# m2301-stereo-output.net
KiCad netlist of a schematic drawn in EAGLE
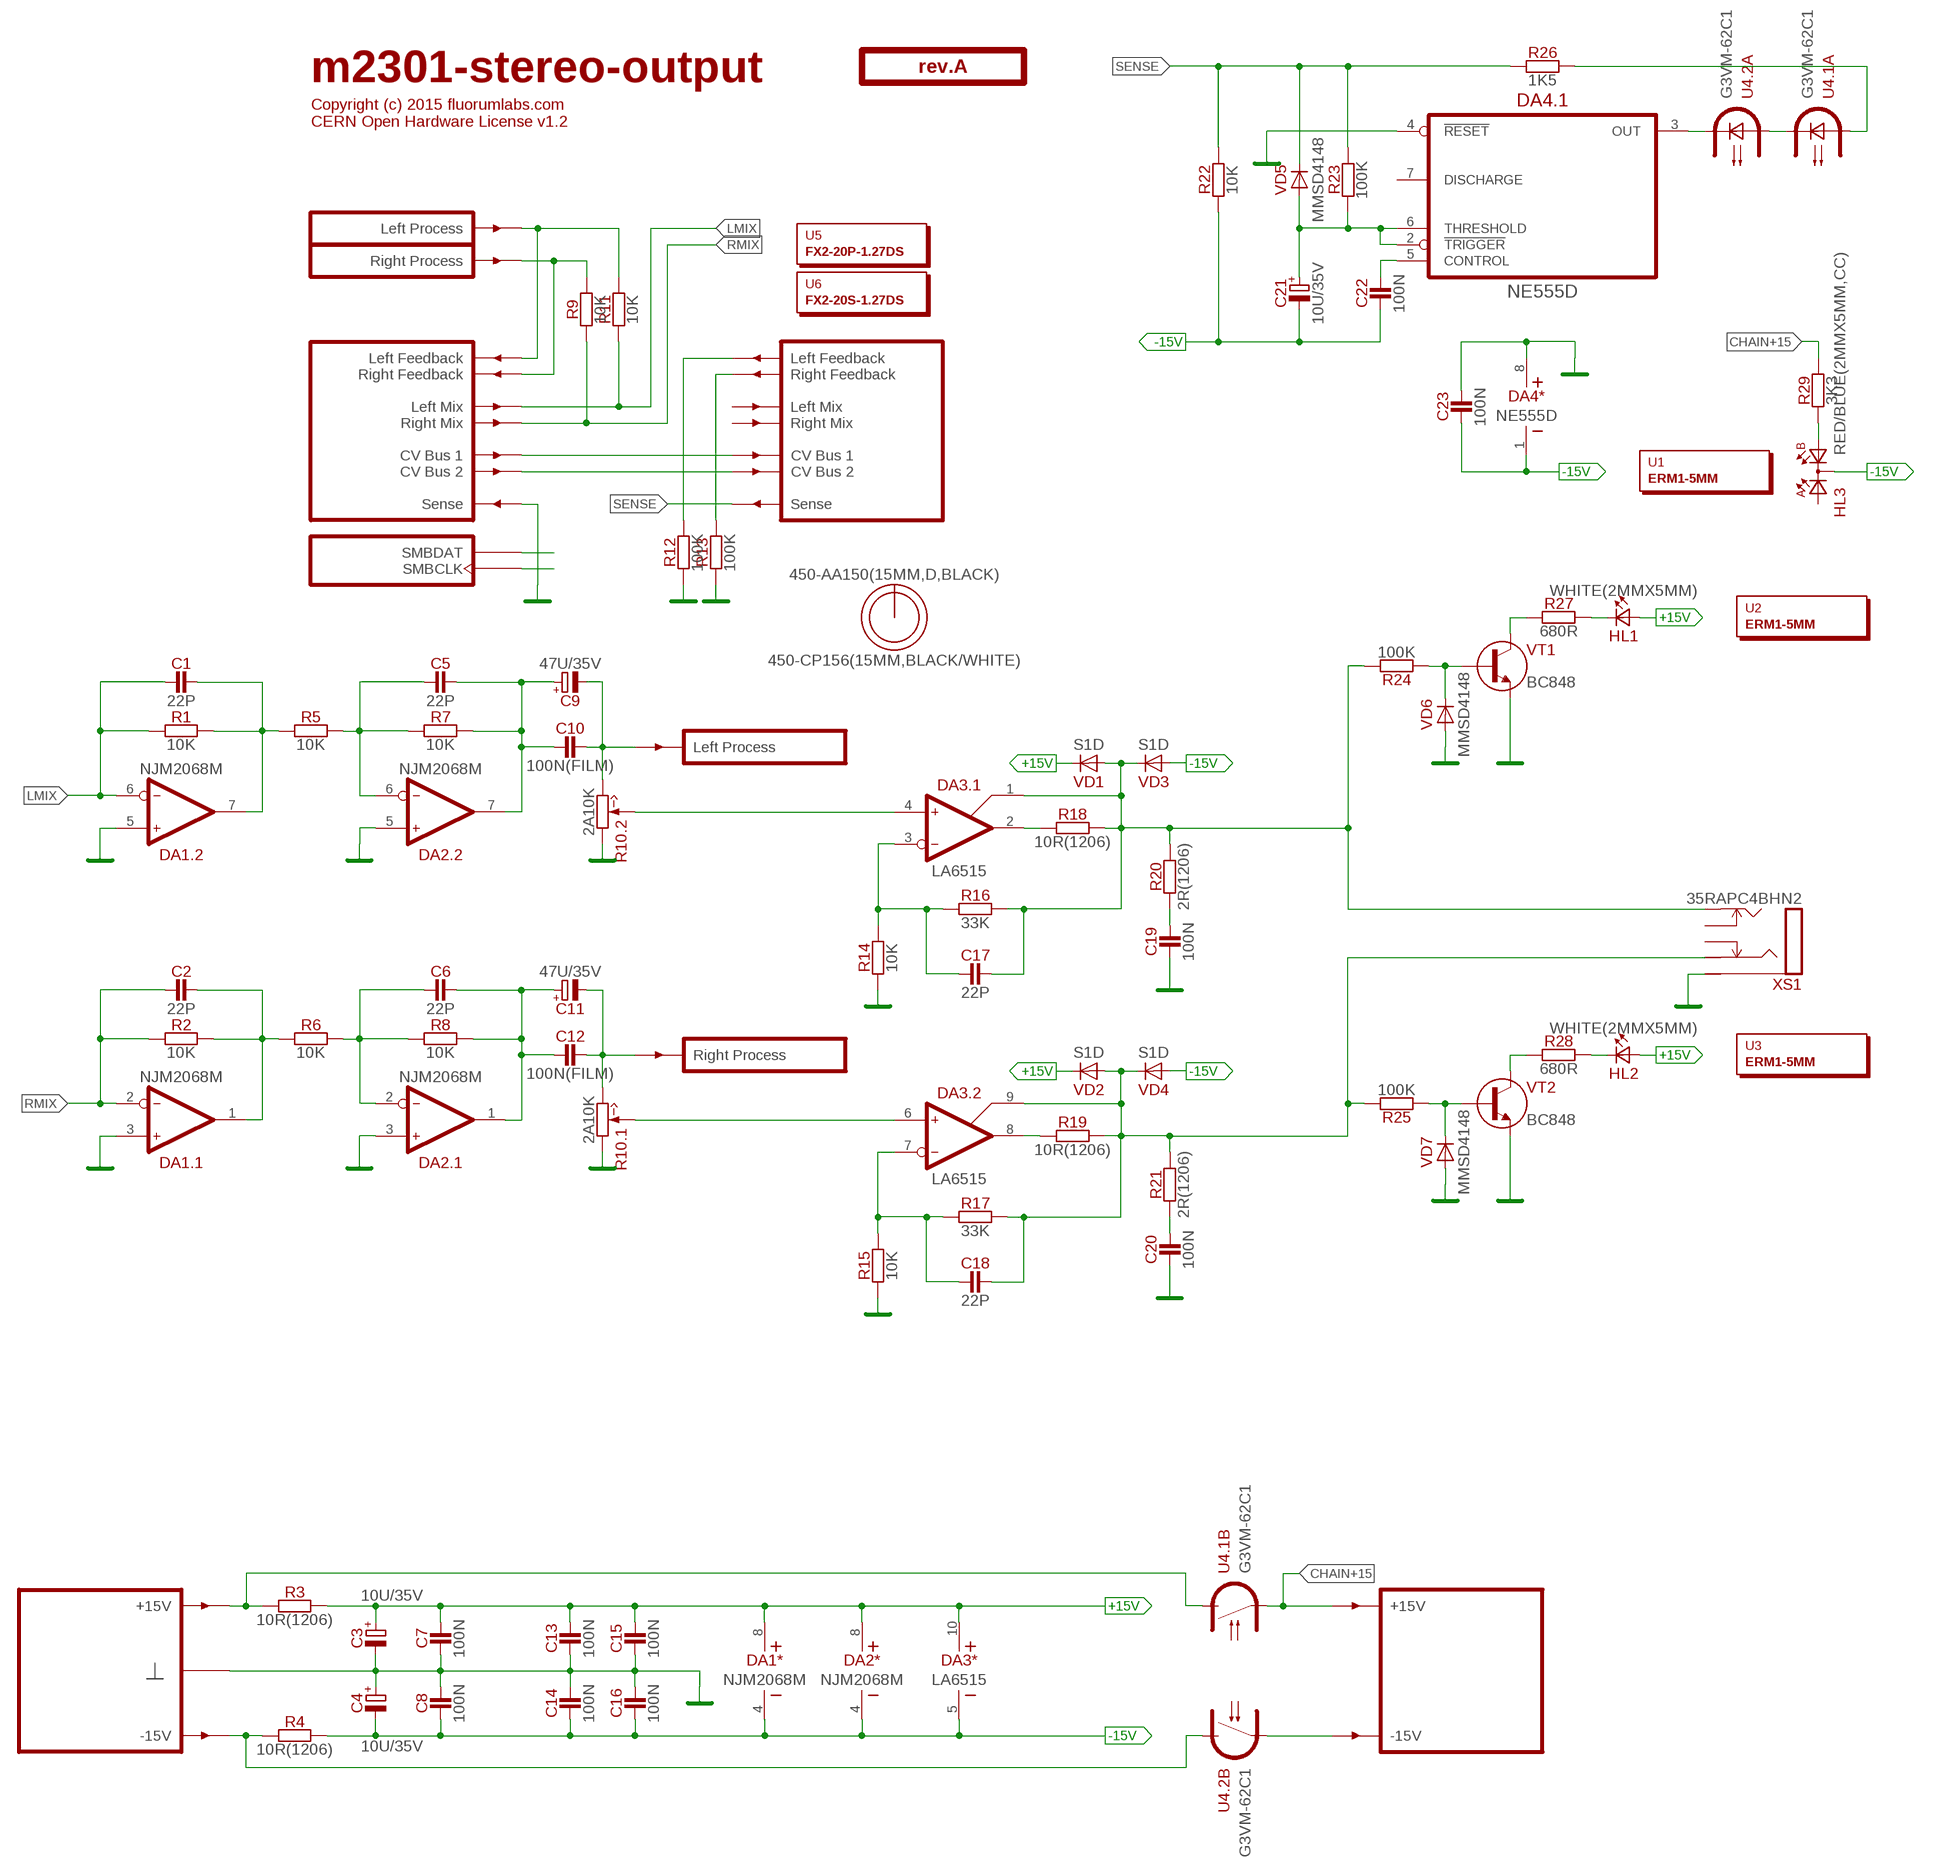
[diagram p0: schematic, sheet 1]

(export (version "E")
  (design (tool "Eeschema 10.0.6"))
  (components
    (comp (ref "C1")
      (value "22P")
      (footprint "eagle-import:C-0805")
      (libsource (lib "eagle-import") (part "?22P"))
    )
    (comp (ref "C2")
      (value "22P")
      (footprint "eagle-import:C-0805")
      (libsource (lib "eagle-import") (part "?22P"))
    )
    (comp (ref "C3")
      (value "10U/35V")
      (footprint "eagle-import:E2-5")
      (libsource (lib "eagle-import") (part "?10U/35V"))
    )
    (comp (ref "C4")
      (value "10U/35V")
      (footprint "eagle-import:E2-5")
      (libsource (lib "eagle-import") (part "?10U/35V"))
    )
    (comp (ref "C5")
      (value "22P")
      (footprint "eagle-import:C-0805")
      (libsource (lib "eagle-import") (part "?22P"))
    )
    (comp (ref "C6")
      (value "22P")
      (footprint "eagle-import:C-0805")
      (libsource (lib "eagle-import") (part "?22P"))
    )
    (comp (ref "C7")
      (value "100N")
      (footprint "eagle-import:C-0805")
      (libsource (lib "eagle-import") (part "?100N"))
    )
    (comp (ref "C8")
      (value "100N")
      (footprint "eagle-import:C-0805")
      (libsource (lib "eagle-import") (part "?100N"))
    )
    (comp (ref "C9")
      (value "47U/35V")
      (footprint "eagle-import:E3,5-8")
      (libsource (lib "eagle-import") (part "?47U/35V"))
    )
    (comp (ref "C10")
      (value "100N(FILM)")
      (footprint "eagle-import:C050-025X075")
      (libsource (lib "eagle-import") (part "?100N(FILM)"))
    )
    (comp (ref "C11")
      (value "47U/35V")
      (footprint "eagle-import:E3,5-8")
      (libsource (lib "eagle-import") (part "?47U/35V"))
    )
    (comp (ref "C12")
      (value "100N(FILM)")
      (footprint "eagle-import:C050-025X075")
      (libsource (lib "eagle-import") (part "?100N(FILM)"))
    )
    (comp (ref "C13")
      (value "100N")
      (footprint "eagle-import:C-0805")
      (libsource (lib "eagle-import") (part "?100N"))
    )
    (comp (ref "C14")
      (value "100N")
      (footprint "eagle-import:C-0805")
      (libsource (lib "eagle-import") (part "?100N"))
    )
    (comp (ref "C15")
      (value "100N")
      (footprint "eagle-import:C-0805")
      (libsource (lib "eagle-import") (part "?100N"))
    )
    (comp (ref "C16")
      (value "100N")
      (footprint "eagle-import:C-0805")
      (libsource (lib "eagle-import") (part "?100N"))
    )
    (comp (ref "C17")
      (value "22P")
      (footprint "eagle-import:C-0805")
      (libsource (lib "eagle-import") (part "?22P"))
    )
    (comp (ref "C18")
      (value "22P")
      (footprint "eagle-import:C-0805")
      (libsource (lib "eagle-import") (part "?22P"))
    )
    (comp (ref "C19")
      (value "100N")
      (footprint "eagle-import:C-0805")
      (libsource (lib "eagle-import") (part "?100N"))
    )
    (comp (ref "C20")
      (value "100N")
      (footprint "eagle-import:C-0805")
      (libsource (lib "eagle-import") (part "?100N"))
    )
    (comp (ref "C21")
      (value "10U/35V")
      (footprint "eagle-import:E2-5")
      (libsource (lib "eagle-import") (part "?10U/35V"))
    )
    (comp (ref "C22")
      (value "100N")
      (footprint "eagle-import:C-0805")
      (libsource (lib "eagle-import") (part "?100N"))
    )
    (comp (ref "C23")
      (value "100N")
      (footprint "eagle-import:C-0805")
      (libsource (lib "eagle-import") (part "?100N"))
    )
    (comp (ref "DA1")
      (value "NJM2068M")
      (footprint "eagle-import:SO-8")
      (libsource (lib "eagle-import") (part "NJM2068M"))
    )
    (comp (ref "DA2")
      (value "NJM2068M")
      (footprint "eagle-import:SO-8")
      (libsource (lib "eagle-import") (part "NJM2068M"))
    )
    (comp (ref "DA3")
      (value "LA6515")
      (footprint "eagle-import:SIL10")
      (libsource (lib "eagle-import") (part "LA6515"))
    )
    (comp (ref "DA4")
      (value "NE555D")
      (footprint "eagle-import:SO-8")
      (libsource (lib "eagle-import") (part "NE555?D"))
    )
    (comp (ref "HL1")
      (value "WHITE(2MMX5MM)")
      (footprint "eagle-import:LED2X5")
      (libsource (lib "eagle-import") (part "?(2MMX5MM)WHITE"))
    )
    (comp (ref "HL2")
      (value "WHITE(2MMX5MM)")
      (footprint "eagle-import:LED2X5")
      (libsource (lib "eagle-import") (part "?(2MMX5MM)WHITE"))
    )
    (comp (ref "HL3")
      (value "RED/BLUE(2MMX5MM,CC)")
      (footprint "eagle-import:LED2X5-3PIN")
      (libsource (lib "eagle-import") (part "?(2MMX5MM,CC)RED/BLUE"))
    )
    (comp (ref "O1")
      (value "TITLE")
      (footprint "eagle-import:EMPTY")
      (libsource (lib "eagle-import") (part "TITLE"))
    )
    (comp (ref "O2")
      (value "450-AA150(15MM,D,BLACK)")
      (footprint "eagle-import:EMPTY")
      (libsource (lib "eagle-import") (part "450-AA?150(15MM,D,BLACK)"))
    )
    (comp (ref "O3")
      (value "450-CP156(15MM,BLACK/WHITE)")
      (footprint "eagle-import:EMPTY")
      (libsource (lib "eagle-import") (part "450-C?P156(15MM,BLACK/WHITE)"))
    )
    (comp (ref "PCB1")
      (value "rev.A")
      (footprint "eagle-import:ST2-BOARD-50")
      (libsource (lib "eagle-import") (part "ST2-BOARD-50-CHAIN"))
    )
    (comp (ref "R1")
      (value "10K")
      (footprint "eagle-import:R-0805")
      (libsource (lib "eagle-import") (part "?10K"))
    )
    (comp (ref "R2")
      (value "10K")
      (footprint "eagle-import:R-0805")
      (libsource (lib "eagle-import") (part "?10K"))
    )
    (comp (ref "R3")
      (value "10R(1206)")
      (footprint "eagle-import:R-1206")
      (libsource (lib "eagle-import") (part "?10R(1206)"))
    )
    (comp (ref "R4")
      (value "10R(1206)")
      (footprint "eagle-import:R-1206")
      (libsource (lib "eagle-import") (part "?10R(1206)"))
    )
    (comp (ref "R5")
      (value "10K")
      (footprint "eagle-import:R-0805")
      (libsource (lib "eagle-import") (part "?10K"))
    )
    (comp (ref "R6")
      (value "10K")
      (footprint "eagle-import:R-0805")
      (libsource (lib "eagle-import") (part "?10K"))
    )
    (comp (ref "R7")
      (value "10K")
      (footprint "eagle-import:R-0805")
      (libsource (lib "eagle-import") (part "?10K"))
    )
    (comp (ref "R8")
      (value "10K")
      (footprint "eagle-import:R-0805")
      (libsource (lib "eagle-import") (part "?10K"))
    )
    (comp (ref "R9")
      (value "10K")
      (footprint "eagle-import:R-0805")
      (libsource (lib "eagle-import") (part "?10K"))
    )
    (comp (ref "R10")
      (value "2A10K")
      (footprint "eagle-import:RV11-DUAL")
      (libsource (lib "eagle-import") (part "2?A10K"))
    )
    (comp (ref "R11")
      (value "10K")
      (footprint "eagle-import:R-0805")
      (libsource (lib "eagle-import") (part "?10K"))
    )
    (comp (ref "R12")
      (value "100K")
      (footprint "eagle-import:R-0805")
      (libsource (lib "eagle-import") (part "?100K"))
    )
    (comp (ref "R13")
      (value "100K")
      (footprint "eagle-import:R-0805")
      (libsource (lib "eagle-import") (part "?100K"))
    )
    (comp (ref "R14")
      (value "10K")
      (footprint "eagle-import:R-0805")
      (libsource (lib "eagle-import") (part "?10K"))
    )
    (comp (ref "R15")
      (value "10K")
      (footprint "eagle-import:R-0805")
      (libsource (lib "eagle-import") (part "?10K"))
    )
    (comp (ref "R16")
      (value "33K")
      (footprint "eagle-import:R-0805")
      (libsource (lib "eagle-import") (part "?33K"))
    )
    (comp (ref "R17")
      (value "33K")
      (footprint "eagle-import:R-0805")
      (libsource (lib "eagle-import") (part "?33K"))
    )
    (comp (ref "R18")
      (value "10R(1206)")
      (footprint "eagle-import:R-1206")
      (libsource (lib "eagle-import") (part "?10R(1206)"))
    )
    (comp (ref "R19")
      (value "10R(1206)")
      (footprint "eagle-import:R-1206")
      (libsource (lib "eagle-import") (part "?10R(1206)"))
    )
    (comp (ref "R20")
      (value "2R(1206)")
      (footprint "eagle-import:R-1206")
      (libsource (lib "eagle-import") (part "?2R(1206)"))
    )
    (comp (ref "R21")
      (value "2R(1206)")
      (footprint "eagle-import:R-1206")
      (libsource (lib "eagle-import") (part "?2R(1206)"))
    )
    (comp (ref "R22")
      (value "10K")
      (footprint "eagle-import:R-0805")
      (libsource (lib "eagle-import") (part "?10K"))
    )
    (comp (ref "R23")
      (value "100K")
      (footprint "eagle-import:R-0805")
      (libsource (lib "eagle-import") (part "?100K"))
    )
    (comp (ref "R24")
      (value "100K")
      (footprint "eagle-import:R-0805")
      (libsource (lib "eagle-import") (part "?100K"))
    )
    (comp (ref "R25")
      (value "100K")
      (footprint "eagle-import:R-0805")
      (libsource (lib "eagle-import") (part "?100K"))
    )
    (comp (ref "R26")
      (value "1K5")
      (footprint "eagle-import:R-0805")
      (libsource (lib "eagle-import") (part "?1K5"))
    )
    (comp (ref "R27")
      (value "680R")
      (footprint "eagle-import:R-0805")
      (libsource (lib "eagle-import") (part "?680R"))
    )
    (comp (ref "R28")
      (value "680R")
      (footprint "eagle-import:R-0805")
      (libsource (lib "eagle-import") (part "?680R"))
    )
    (comp (ref "R29")
      (value "3K3")
      (footprint "eagle-import:R-0805")
      (libsource (lib "eagle-import") (part "?3K3"))
    )
    (comp (ref "U1")
      (value "ERM1-5MM")
      (footprint "eagle-import:EMPTY")
      (libsource (lib "eagle-import") (part "?ERM1-5MM"))
    )
    (comp (ref "U2")
      (value "ERM1-5MM")
      (footprint "eagle-import:EMPTY")
      (libsource (lib "eagle-import") (part "?ERM1-5MM"))
    )
    (comp (ref "U3")
      (value "ERM1-5MM")
      (footprint "eagle-import:EMPTY")
      (libsource (lib "eagle-import") (part "?ERM1-5MM"))
    )
    (comp (ref "U4")
      (value "G3VM-62C1")
      (footprint "eagle-import:DIL08")
      (libsource (lib "eagle-import") (part "G3VM-?2C61"))
    )
    (comp (ref "U5")
      (value "FX2-20P-1.27DS")
      (footprint "eagle-import:EMPTY")
      (libsource (lib "eagle-import") (part "?FX2-20P-1.27DS"))
    )
    (comp (ref "U6")
      (value "FX2-20S-1.27DS")
      (footprint "eagle-import:EMPTY")
      (libsource (lib "eagle-import") (part "?FX2-20S-1.27DS"))
    )
    (comp (ref "VD1")
      (value "S1D")
      (footprint "eagle-import:DO214AC")
      (libsource (lib "eagle-import") (part "?S1D"))
    )
    (comp (ref "VD2")
      (value "S1D")
      (footprint "eagle-import:DO214AC")
      (libsource (lib "eagle-import") (part "?S1D"))
    )
    (comp (ref "VD3")
      (value "S1D")
      (footprint "eagle-import:DO214AC")
      (libsource (lib "eagle-import") (part "?S1D"))
    )
    (comp (ref "VD4")
      (value "S1D")
      (footprint "eagle-import:DO214AC")
      (libsource (lib "eagle-import") (part "?S1D"))
    )
    (comp (ref "VD5")
      (value "MMSD4148")
      (footprint "eagle-import:SOD123")
      (libsource (lib "eagle-import") (part "?MMSD4148"))
    )
    (comp (ref "VD6")
      (value "MMSD4148")
      (footprint "eagle-import:SOD123")
      (libsource (lib "eagle-import") (part "?MMSD4148"))
    )
    (comp (ref "VD7")
      (value "MMSD4148")
      (footprint "eagle-import:SOD123")
      (libsource (lib "eagle-import") (part "?MMSD4148"))
    )
    (comp (ref "VT1")
      (value "BC848")
      (footprint "eagle-import:SOT23")
      (libsource (lib "eagle-import") (part "?BC848"))
    )
    (comp (ref "VT2")
      (value "BC848")
      (footprint "eagle-import:SOT23")
      (libsource (lib "eagle-import") (part "?BC848"))
    )
    (comp (ref "XS1")
      (value "35RAPC4BHN2")
      (footprint "eagle-import:35RAP")
      (libsource (lib "eagle-import") (part "35RAPC4BHN2"))
    )
  )
  (nets
    (net (code "1") (name "+15V") (class "Default")
      (node (ref "C13") (pin "2") (pinfunction "2_2") (pintype "passive"))
      (node (ref "C15") (pin "2") (pinfunction "2_2") (pintype "passive"))
      (node (ref "C3") (pin "+") (pinfunction "+_+") (pintype "passive"))
      (node (ref "C7") (pin "2") (pinfunction "2_2") (pintype "passive"))
      (node (ref "DA1") (pin "8") (pinfunction "V+_8") (pintype "power_in"))
      (node (ref "DA2") (pin "8") (pinfunction "V+_8") (pintype "power_in"))
      (node (ref "DA3") (pin "10") (pinfunction "V+_10") (pintype "power_in"))
      (node (ref "HL1") (pin "A") (pinfunction "A_A") (pintype "passive"))
      (node (ref "HL2") (pin "A") (pinfunction "A_A") (pintype "passive"))
      (node (ref "R3") (pin "2") (pinfunction "2_2") (pintype "passive"))
      (node (ref "VD1") (pin "C") (pinfunction "C_C") (pintype "passive"))
      (node (ref "VD2") (pin "C") (pinfunction "C_C") (pintype "passive"))
    )
    (net (code "2") (name "-15V") (class "Default")
      (node (ref "C14") (pin "1") (pinfunction "1_1") (pintype "passive"))
      (node (ref "C16") (pin "1") (pinfunction "1_1") (pintype "passive"))
      (node (ref "C21") (pin "-") (pinfunction "-_-") (pintype "passive"))
      (node (ref "C22") (pin "1") (pinfunction "1_1") (pintype "passive"))
      (node (ref "C23") (pin "1") (pinfunction "1_1") (pintype "passive"))
      (node (ref "C4") (pin "-") (pinfunction "-_-") (pintype "passive"))
      (node (ref "C8") (pin "1") (pinfunction "1_1") (pintype "passive"))
      (node (ref "DA1") (pin "4") (pinfunction "V-_4") (pintype "power_in"))
      (node (ref "DA2") (pin "4") (pinfunction "V-_4") (pintype "power_in"))
      (node (ref "DA3") (pin "5") (pinfunction "V-_5") (pintype "power_in"))
      (node (ref "DA4") (pin "1") (pinfunction "V-_1") (pintype "power_in"))
      (node (ref "HL3") (pin "K") (pinfunction "K_K") (pintype "passive"))
      (node (ref "R22") (pin "1") (pinfunction "1_1") (pintype "passive"))
      (node (ref "R4") (pin "2") (pinfunction "2_2") (pintype "passive"))
      (node (ref "VD3") (pin "A") (pinfunction "A_A") (pintype "passive"))
      (node (ref "VD4") (pin "A") (pinfunction "A_A") (pintype "passive"))
    )
    (net (code "3") (name "CHAIN+15") (class "Default")
      (node (ref "PCB1") (pin "A+15'") (pinfunction "P+15V_A+15'") (pintype "bidirectional"))
      (node (ref "PCB1") (pin "B+15'") (pinfunction "P+15V_B+15'") (pintype "bidirectional"))
      (node (ref "R29") (pin "2") (pinfunction "2_2") (pintype "passive"))
      (node (ref "U4") (pin "7") (pinfunction "S2_7") (pintype "passive"))
    )
    (net (code "4") (name "GND") (class "Default")
      (node (ref "C13") (pin "1") (pinfunction "1_1") (pintype "passive"))
      (node (ref "C14") (pin "2") (pinfunction "2_2") (pintype "passive"))
      (node (ref "C15") (pin "1") (pinfunction "1_1") (pintype "passive"))
      (node (ref "C16") (pin "2") (pinfunction "2_2") (pintype "passive"))
      (node (ref "C19") (pin "1") (pinfunction "1_1") (pintype "passive"))
      (node (ref "C20") (pin "1") (pinfunction "1_1") (pintype "passive"))
      (node (ref "C23") (pin "2") (pinfunction "2_2") (pintype "passive"))
      (node (ref "C3") (pin "-") (pinfunction "-_-") (pintype "passive"))
      (node (ref "C4") (pin "+") (pinfunction "+_+") (pintype "passive"))
      (node (ref "C7") (pin "1") (pinfunction "1_1") (pintype "passive"))
      (node (ref "C8") (pin "2") (pinfunction "2_2") (pintype "passive"))
      (node (ref "DA1") (pin "3") (pinfunction "IN+_3") (pintype "input"))
      (node (ref "DA1") (pin "5") (pinfunction "IN+_5") (pintype "input"))
      (node (ref "DA2") (pin "3") (pinfunction "IN+_3") (pintype "input"))
      (node (ref "DA2") (pin "5") (pinfunction "IN+_5") (pintype "input"))
      (node (ref "DA4") (pin "4") (pinfunction "~{RESET}_4") (pintype "input"))
      (node (ref "DA4") (pin "8") (pinfunction "V+_8") (pintype "power_in"))
      (node (ref "PCB1") (pin "B4") (pinfunction "GND_B4") (pintype "bidirectional"))
      (node (ref "PCB1") (pin "B4'") (pinfunction "GND_B4'") (pintype "bidirectional"))
      (node (ref "PCB1") (pin "B5") (pinfunction "GND_B5") (pintype "bidirectional"))
      (node (ref "PCB1") (pin "B5'") (pinfunction "GND_B5'") (pintype "bidirectional"))
      (node (ref "PCB1") (pin "B6") (pinfunction "GND_B6") (pintype "bidirectional"))
      (node (ref "PCB1") (pin "B6'") (pinfunction "GND_B6'") (pintype "bidirectional"))
      (node (ref "PCB1") (pin "B7") (pinfunction "GND_B7") (pintype "bidirectional"))
      (node (ref "PCB1") (pin "B7'") (pinfunction "GND_B7'") (pintype "bidirectional"))
      (node (ref "PCB1") (pin "B8") (pinfunction "GND_B8") (pintype "bidirectional"))
      (node (ref "PCB1") (pin "B8'") (pinfunction "GND_B8'") (pintype "bidirectional"))
      (node (ref "PCB1") (pin "BSENSE") (pinfunction "SENSE_BSENSE") (pintype "bidirectional"))
      (node (ref "R10") (pin "1") (pinfunction "CCW_1") (pintype "passive"))
      (node (ref "R10") (pin "1'") (pinfunction "CCW_1'") (pintype "passive"))
      (node (ref "R12") (pin "1") (pinfunction "1_1") (pintype "passive"))
      (node (ref "R13") (pin "1") (pinfunction "1_1") (pintype "passive"))
      (node (ref "R14") (pin "1") (pinfunction "1_1") (pintype "passive"))
      (node (ref "R15") (pin "1") (pinfunction "1_1") (pintype "passive"))
      (node (ref "VD6") (pin "A") (pinfunction "A_A") (pintype "passive"))
      (node (ref "VD7") (pin "A") (pinfunction "A_A") (pintype "passive"))
      (node (ref "VT1") (pin "2") (pinfunction "E_2") (pintype "passive"))
      (node (ref "VT2") (pin "2") (pinfunction "E_2") (pintype "passive"))
      (node (ref "XS1") (pin "1") (pinfunction "S_1") (pintype "passive"))
    )
    (net (code "5") (name "LMIX") (class "Default")
      (node (ref "C1") (pin "1") (pinfunction "1_1") (pintype "passive"))
      (node (ref "DA1") (pin "6") (pinfunction "IN-_6") (pintype "input"))
      (node (ref "PCB1") (pin "ALMIX") (pinfunction "LMIX_ALMIX") (pintype "bidirectional"))
      (node (ref "R1") (pin "1") (pinfunction "1_1") (pintype "passive"))
      (node (ref "R11") (pin "1") (pinfunction "1_1") (pintype "passive"))
    )
    (net (code "6") (name "Net-(C19-Pad2)") (class "Default")
      (node (ref "C19") (pin "2") (pinfunction "2_2") (pintype "passive"))
      (node (ref "R20") (pin "1") (pinfunction "1_1") (pintype "passive"))
    )
    (net (code "7") (name "Net-(C20-Pad2)") (class "Default")
      (node (ref "C20") (pin "2") (pinfunction "2_2") (pintype "passive"))
      (node (ref "R21") (pin "1") (pinfunction "1_1") (pintype "passive"))
    )
    (net (code "8") (name "Net-(DA1B-OUT)") (class "Default")
      (node (ref "C2") (pin "2") (pinfunction "2_2") (pintype "passive"))
      (node (ref "DA1") (pin "1") (pinfunction "OUT_1") (pintype "output"))
      (node (ref "R2") (pin "2") (pinfunction "2_2") (pintype "passive"))
      (node (ref "R6") (pin "1") (pinfunction "1_1") (pintype "passive"))
    )
    (net (code "9") (name "Net-(DA1C-OUT)") (class "Default")
      (node (ref "C1") (pin "2") (pinfunction "2_2") (pintype "passive"))
      (node (ref "DA1") (pin "7") (pinfunction "OUT_7") (pintype "output"))
      (node (ref "R1") (pin "2") (pinfunction "2_2") (pintype "passive"))
      (node (ref "R5") (pin "1") (pinfunction "1_1") (pintype "passive"))
    )
    (net (code "10") (name "Net-(DA2B-IN-)") (class "Default")
      (node (ref "C6") (pin "1") (pinfunction "1_1") (pintype "passive"))
      (node (ref "DA2") (pin "2") (pinfunction "IN-_2") (pintype "input"))
      (node (ref "R6") (pin "2") (pinfunction "2_2") (pintype "passive"))
      (node (ref "R8") (pin "1") (pinfunction "1_1") (pintype "passive"))
    )
    (net (code "11") (name "Net-(DA2B-OUT)") (class "Default")
      (node (ref "C11") (pin "+") (pinfunction "+_+") (pintype "passive"))
      (node (ref "C12") (pin "1") (pinfunction "1_1") (pintype "passive"))
      (node (ref "C6") (pin "2") (pinfunction "2_2") (pintype "passive"))
      (node (ref "DA2") (pin "1") (pinfunction "OUT_1") (pintype "output"))
      (node (ref "R8") (pin "2") (pinfunction "2_2") (pintype "passive"))
    )
    (net (code "12") (name "Net-(DA2C-IN-)") (class "Default")
      (node (ref "C5") (pin "1") (pinfunction "1_1") (pintype "passive"))
      (node (ref "DA2") (pin "6") (pinfunction "IN-_6") (pintype "input"))
      (node (ref "R5") (pin "2") (pinfunction "2_2") (pintype "passive"))
      (node (ref "R7") (pin "1") (pinfunction "1_1") (pintype "passive"))
    )
    (net (code "13") (name "Net-(DA2C-OUT)") (class "Default")
      (node (ref "C10") (pin "1") (pinfunction "1_1") (pintype "passive"))
      (node (ref "C5") (pin "2") (pinfunction "2_2") (pintype "passive"))
      (node (ref "C9") (pin "+") (pinfunction "+_+") (pintype "passive"))
      (node (ref "DA2") (pin "7") (pinfunction "OUT_7") (pintype "output"))
      (node (ref "R7") (pin "2") (pinfunction "2_2") (pintype "passive"))
    )
    (net (code "14") (name "Net-(DA3B-IN+)") (class "Default")
      (node (ref "DA3") (pin "4") (pinfunction "IN+_4") (pintype "input"))
      (node (ref "R10") (pin "2'") (pinfunction "W_2'") (pintype "passive"))
    )
    (net (code "15") (name "Net-(DA3B-IN-)") (class "Default")
      (node (ref "C17") (pin "1") (pinfunction "1_1") (pintype "passive"))
      (node (ref "DA3") (pin "3") (pinfunction "IN-_3") (pintype "input"))
      (node (ref "R14") (pin "2") (pinfunction "2_2") (pintype "passive"))
      (node (ref "R16") (pin "1") (pinfunction "1_1") (pintype "passive"))
    )
    (net (code "16") (name "Net-(DA3B-OUT)") (class "Default")
      (node (ref "DA3") (pin "2") (pinfunction "OUT_2") (pintype "output"))
      (node (ref "R18") (pin "1") (pinfunction "1_1") (pintype "passive"))
    )
    (net (code "17") (name "Net-(DA3B-SENSE)") (class "Default")
      (node (ref "C17") (pin "2") (pinfunction "2_2") (pintype "passive"))
      (node (ref "DA3") (pin "1") (pinfunction "SENSE_1") (pintype "output"))
      (node (ref "R16") (pin "2") (pinfunction "2_2") (pintype "passive"))
      (node (ref "R18") (pin "2") (pinfunction "2_2") (pintype "passive"))
      (node (ref "R20") (pin "2") (pinfunction "2_2") (pintype "passive"))
      (node (ref "R24") (pin "2") (pinfunction "2_2") (pintype "passive"))
      (node (ref "VD1") (pin "A") (pinfunction "A_A") (pintype "passive"))
      (node (ref "VD3") (pin "C") (pinfunction "C_C") (pintype "passive"))
      (node (ref "XS1") (pin "2") (pinfunction "T_2") (pintype "passive"))
    )
    (net (code "18") (name "Net-(DA3C-IN+)") (class "Default")
      (node (ref "DA3") (pin "6") (pinfunction "IN+_6") (pintype "input"))
      (node (ref "R10") (pin "2") (pinfunction "W_2") (pintype "passive"))
    )
    (net (code "19") (name "Net-(DA3C-IN-)") (class "Default")
      (node (ref "C18") (pin "1") (pinfunction "1_1") (pintype "passive"))
      (node (ref "DA3") (pin "7") (pinfunction "IN-_7") (pintype "input"))
      (node (ref "R15") (pin "2") (pinfunction "2_2") (pintype "passive"))
      (node (ref "R17") (pin "1") (pinfunction "1_1") (pintype "passive"))
    )
    (net (code "20") (name "Net-(DA3C-OUT)") (class "Default")
      (node (ref "DA3") (pin "8") (pinfunction "OUT_8") (pintype "output"))
      (node (ref "R19") (pin "1") (pinfunction "1_1") (pintype "passive"))
    )
    (net (code "21") (name "Net-(DA3C-SENSE)") (class "Default")
      (node (ref "C18") (pin "2") (pinfunction "2_2") (pintype "passive"))
      (node (ref "DA3") (pin "9") (pinfunction "SENSE_9") (pintype "output"))
      (node (ref "R17") (pin "2") (pinfunction "2_2") (pintype "passive"))
      (node (ref "R19") (pin "2") (pinfunction "2_2") (pintype "passive"))
      (node (ref "R21") (pin "2") (pinfunction "2_2") (pintype "passive"))
      (node (ref "R25") (pin "2") (pinfunction "2_2") (pintype "passive"))
      (node (ref "VD2") (pin "A") (pinfunction "A_A") (pintype "passive"))
      (node (ref "VD4") (pin "C") (pinfunction "C_C") (pintype "passive"))
      (node (ref "XS1") (pin "3") (pinfunction "R_3") (pintype "passive"))
    )
    (net (code "22") (name "Net-(DA4B-CONTROL)") (class "Default")
      (node (ref "C22") (pin "2") (pinfunction "2_2") (pintype "passive"))
      (node (ref "DA4") (pin "5") (pinfunction "CONTROL_5") (pintype "bidirectional"))
    )
    (net (code "23") (name "Net-(DA4B-OUT)") (class "Default")
      (node (ref "DA4") (pin "3") (pinfunction "OUT_3") (pintype "bidirectional"))
      (node (ref "U4") (pin "4") (pinfunction "C_4") (pintype "passive"))
    )
    (net (code "24") (name "Net-(DA4B-THRESHOLD)") (class "Default")
      (node (ref "C21") (pin "+") (pinfunction "+_+") (pintype "passive"))
      (node (ref "DA4") (pin "2") (pinfunction "~{TRIGGER}_2") (pintype "bidirectional"))
      (node (ref "DA4") (pin "6") (pinfunction "THRESHOLD_6") (pintype "bidirectional"))
      (node (ref "R23") (pin "1") (pinfunction "1_1") (pintype "passive"))
      (node (ref "VD5") (pin "A") (pinfunction "A_A") (pintype "passive"))
    )
    (net (code "25") (name "Net-(HL1-C)") (class "Default")
      (node (ref "HL1") (pin "K") (pinfunction "C_K") (pintype "passive"))
      (node (ref "R27") (pin "2") (pinfunction "2_2") (pintype "passive"))
    )
    (net (code "26") (name "Net-(HL2-C)") (class "Default")
      (node (ref "HL2") (pin "K") (pinfunction "C_K") (pintype "passive"))
      (node (ref "R28") (pin "2") (pinfunction "2_2") (pintype "passive"))
    )
    (net (code "27") (name "Net-(HL3-PadA2)") (class "Default")
      (node (ref "HL3") (pin "A2") (pinfunction "A2_A2") (pintype "passive"))
      (node (ref "R29") (pin "1") (pinfunction "1_1") (pintype "passive"))
    )
    (net (code "28") (name "Net-(PCB1C-INL)") (class "Default")
      (node (ref "PCB1") (pin "ALFBK") (pinfunction "LFBK_ALFBK") (pintype "bidirectional"))
      (node (ref "PCB1") (pin "BINL") (pinfunction "INL_BINL") (pintype "bidirectional"))
      (node (ref "R11") (pin "2") (pinfunction "2_2") (pintype "passive"))
    )
    (net (code "29") (name "Net-(PCB1D-INR)") (class "Default")
      (node (ref "PCB1") (pin "ARFBK") (pinfunction "RFBK_ARFBK") (pintype "bidirectional"))
      (node (ref "PCB1") (pin "BINR") (pinfunction "INR_BINR") (pintype "bidirectional"))
      (node (ref "R9") (pin "2") (pinfunction "2_2") (pintype "passive"))
    )
    (net (code "30") (name "Net-(PCB1E-OUTL)") (class "Default")
      (node (ref "C10") (pin "2") (pinfunction "2_2") (pintype "passive"))
      (node (ref "C9") (pin "-") (pinfunction "-_-") (pintype "passive"))
      (node (ref "PCB1") (pin "BOUTL'") (pinfunction "OUTL_BOUTL'") (pintype "bidirectional"))
      (node (ref "R10") (pin "3'") (pinfunction "CW_3'") (pintype "passive"))
    )
    (net (code "31") (name "Net-(PCB1F-OUTR)") (class "Default")
      (node (ref "C11") (pin "-") (pinfunction "-_-") (pintype "passive"))
      (node (ref "C12") (pin "2") (pinfunction "2_2") (pintype "passive"))
      (node (ref "PCB1") (pin "BOUTR'") (pinfunction "OUTR_BOUTR'") (pintype "bidirectional"))
      (node (ref "R10") (pin "3") (pinfunction "CW_3") (pintype "passive"))
    )
    (net (code "32") (name "Net-(PCB1G-CV1)") (class "Default")
      (node (ref "PCB1") (pin "ACV1") (pinfunction "CV1_ACV1") (pintype "bidirectional"))
      (node (ref "PCB1") (pin "ACV1'") (pinfunction "CV1'_ACV1'") (pintype "bidirectional"))
    )
    (net (code "33") (name "Net-(PCB1G-CV2)") (class "Default")
      (node (ref "PCB1") (pin "ACV2") (pinfunction "CV2_ACV2") (pintype "bidirectional"))
      (node (ref "PCB1") (pin "ACV2'") (pinfunction "CV2'_ACV2'") (pintype "bidirectional"))
    )
    (net (code "34") (name "Net-(PCB1H-LFBK')") (class "Default")
      (node (ref "PCB1") (pin "ALFBK'") (pinfunction "LFBK'_ALFBK'") (pintype "bidirectional"))
      (node (ref "R12") (pin "2") (pinfunction "2_2") (pintype "passive"))
    )
    (net (code "35") (name "Net-(PCB1H-RFBK')") (class "Default")
      (node (ref "PCB1") (pin "ARFBK'") (pinfunction "RFBK'_ARFBK'") (pintype "bidirectional"))
      (node (ref "R13") (pin "2") (pinfunction "2_2") (pintype "passive"))
    )
    (net (code "36") (name "Net-(PCB1I-SMBCLK-PadASMBCLK')") (class "Default")
      (node (ref "PCB1") (pin "ASMBCLK") (pinfunction "SMBCLK_ASMBCLK") (pintype "bidirectional"))
      (node (ref "PCB1") (pin "ASMBCLK'") (pinfunction "SMBCLK_ASMBCLK'") (pintype "bidirectional"))
    )
    (net (code "37") (name "Net-(PCB1I-SMBDAT-PadASMBDAT')") (class "Default")
      (node (ref "PCB1") (pin "ASMBDAT") (pinfunction "SMBDAT_ASMBDAT") (pintype "bidirectional"))
      (node (ref "PCB1") (pin "ASMBDAT'") (pinfunction "SMBDAT_ASMBDAT'") (pintype "bidirectional"))
    )
    (net (code "38") (name "Net-(U4A-A)") (class "Default")
      (node (ref "R26") (pin "2") (pinfunction "2_2") (pintype "passive"))
      (node (ref "U4") (pin "1") (pinfunction "A_1") (pintype "passive"))
    )
    (net (code "39") (name "Net-(U4A-C)") (class "Default")
      (node (ref "U4") (pin "2") (pinfunction "C_2") (pintype "passive"))
      (node (ref "U4") (pin "3") (pinfunction "A_3") (pintype "passive"))
    )
    (net (code "40") (name "Net-(U4B-S1)") (class "Default")
      (node (ref "PCB1") (pin "A+15") (pinfunction "P+15V_A+15") (pintype "bidirectional"))
      (node (ref "PCB1") (pin "B+15") (pinfunction "P+15V_B+15") (pintype "bidirectional"))
      (node (ref "R3") (pin "1") (pinfunction "1_1") (pintype "passive"))
      (node (ref "U4") (pin "8") (pinfunction "S1_8") (pintype "passive"))
    )
    (net (code "41") (name "Net-(U4D-S1)") (class "Default")
      (node (ref "PCB1") (pin "A-15") (pinfunction "P-15V_A-15") (pintype "bidirectional"))
      (node (ref "PCB1") (pin "B-15") (pinfunction "P-15V_B-15") (pintype "bidirectional"))
      (node (ref "R4") (pin "1") (pinfunction "1_1") (pintype "passive"))
      (node (ref "U4") (pin "6") (pinfunction "S1_6") (pintype "passive"))
    )
    (net (code "42") (name "Net-(U4D-S2)") (class "Default")
      (node (ref "PCB1") (pin "A-15'") (pinfunction "P-15V_A-15'") (pintype "bidirectional"))
      (node (ref "PCB1") (pin "B-15'") (pinfunction "P-15V_B-15'") (pintype "bidirectional"))
      (node (ref "U4") (pin "5") (pinfunction "S2_5") (pintype "passive"))
    )
    (net (code "43") (name "Net-(VT1-B)") (class "Default")
      (node (ref "R24") (pin "1") (pinfunction "1_1") (pintype "passive"))
      (node (ref "VD6") (pin "C") (pinfunction "C_C") (pintype "passive"))
      (node (ref "VT1") (pin "1") (pinfunction "B_1") (pintype "passive"))
    )
    (net (code "44") (name "Net-(VT1-C)") (class "Default")
      (node (ref "R27") (pin "1") (pinfunction "1_1") (pintype "passive"))
      (node (ref "VT1") (pin "3") (pinfunction "C_3") (pintype "passive"))
    )
    (net (code "45") (name "Net-(VT2-B)") (class "Default")
      (node (ref "R25") (pin "1") (pinfunction "1_1") (pintype "passive"))
      (node (ref "VD7") (pin "C") (pinfunction "C_C") (pintype "passive"))
      (node (ref "VT2") (pin "1") (pinfunction "B_1") (pintype "passive"))
    )
    (net (code "46") (name "Net-(VT2-C)") (class "Default")
      (node (ref "R28") (pin "1") (pinfunction "1_1") (pintype "passive"))
      (node (ref "VT2") (pin "3") (pinfunction "C_3") (pintype "passive"))
    )
    (net (code "47") (name "RMIX") (class "Default")
      (node (ref "C2") (pin "1") (pinfunction "1_1") (pintype "passive"))
      (node (ref "DA1") (pin "2") (pinfunction "IN-_2") (pintype "input"))
      (node (ref "PCB1") (pin "ARMIX") (pinfunction "RMIX_ARMIX") (pintype "bidirectional"))
      (node (ref "R2") (pin "1") (pinfunction "1_1") (pintype "passive"))
      (node (ref "R9") (pin "1") (pinfunction "1_1") (pintype "passive"))
    )
    (net (code "48") (name "SENSE") (class "Default")
      (node (ref "PCB1") (pin "BSENSE'") (pinfunction "SENSE'_BSENSE'") (pintype "bidirectional"))
      (node (ref "R22") (pin "2") (pinfunction "2_2") (pintype "passive"))
      (node (ref "R23") (pin "2") (pinfunction "2_2") (pintype "passive"))
      (node (ref "R26") (pin "1") (pinfunction "1_1") (pintype "passive"))
      (node (ref "VD5") (pin "C") (pinfunction "C_C") (pintype "passive"))
    )
    (net (code "49") (name "unconnected-(DA4B-DISCHARGE-Pad7)") (class "Default")
      (node (ref "DA4") (pin "7") (pinfunction "DISCHARGE_7") (pintype "bidirectional"))
    )
    (net (code "50") (name "unconnected-(HL3-PadA1)") (class "Default")
      (node (ref "HL3") (pin "A1") (pinfunction "A1_A1") (pintype "passive"))
    )
    (net (code "51") (name "unconnected-(PCB1H-LMIX'-PadALMIX')") (class "Default")
      (node (ref "PCB1") (pin "ALMIX'") (pinfunction "LMIX'_ALMIX'") (pintype "bidirectional"))
    )
    (net (code "52") (name "unconnected-(PCB1H-RMIX'-PadARMIX')") (class "Default")
      (node (ref "PCB1") (pin "ARMIX'") (pinfunction "RMIX'_ARMIX'") (pintype "bidirectional"))
    )
    (net (code "53") (name "unconnected-(XS1-RN-Pad11)") (class "Default")
      (node (ref "XS1") (pin "11") (pinfunction "RN_11") (pintype "passive"))
    )
    (net (code "54") (name "unconnected-(XS1-TN-Pad10)") (class "Default")
      (node (ref "XS1") (pin "10") (pinfunction "TN_10") (pintype "passive"))
    )
  )
)
